# EE318.net
KiCad netlist of a schematic drawn in Altium Designer
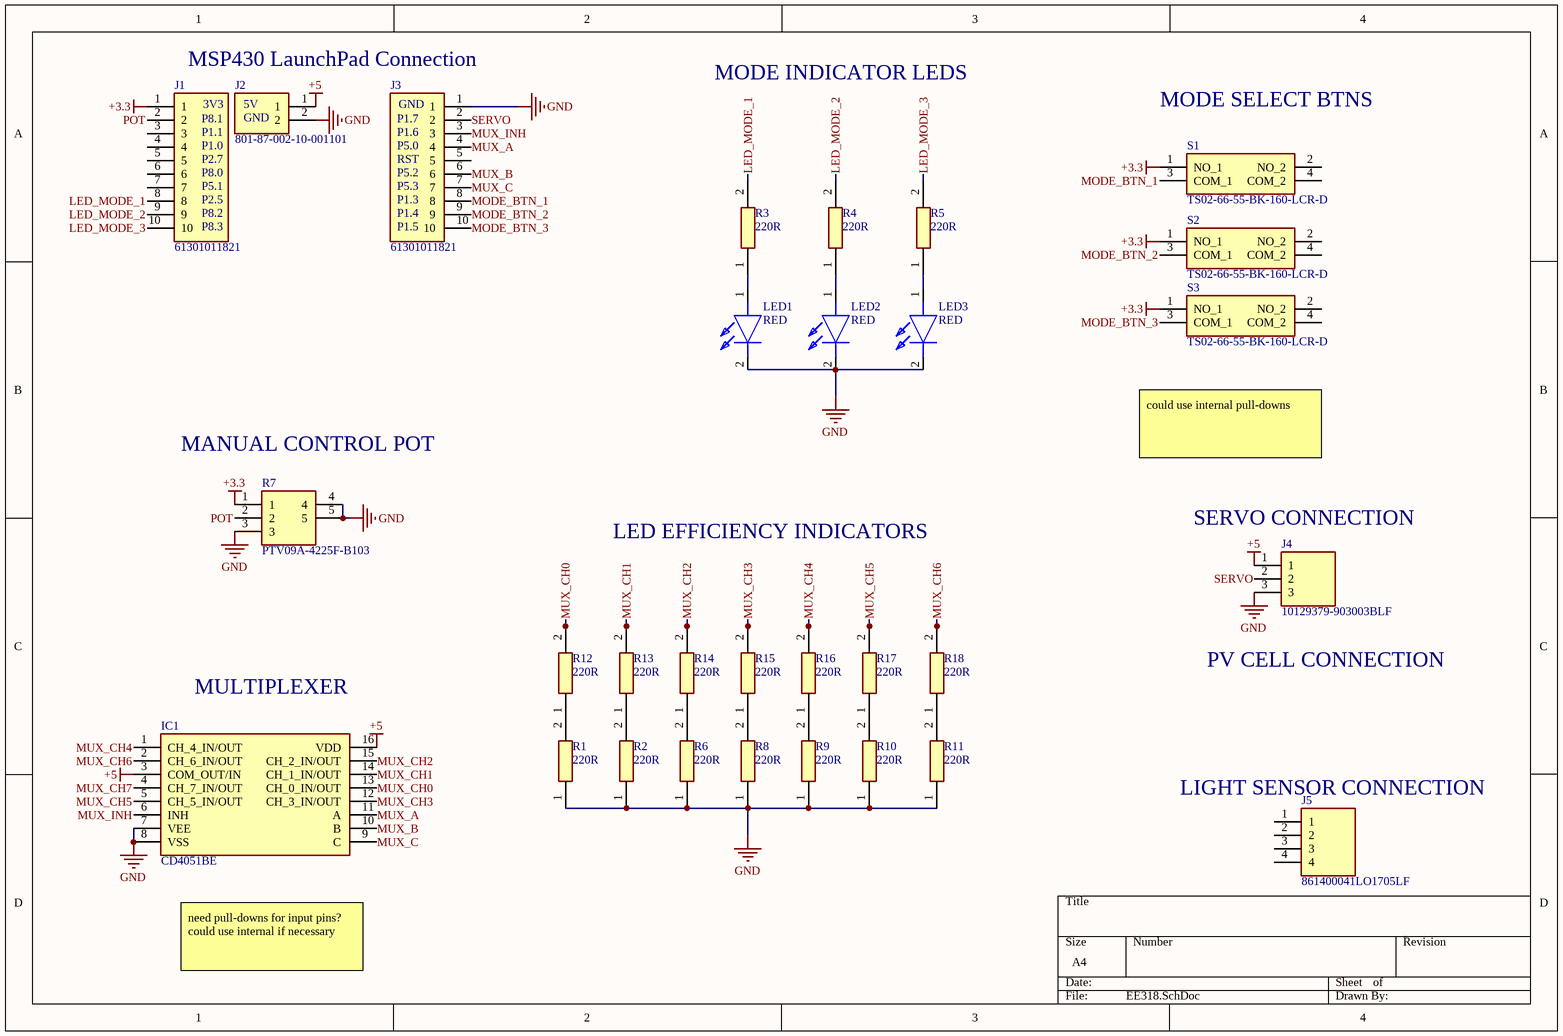
[diagram p0: EE318.SchDoc]

(export (version "E")
  (design (tool "Eeschema 10.0.6"))
  (components
    (comp (ref "IC1")
      (value "CD4051BE")
      (footprint "EE318-PcbLib:DIP794W53P254L1930H508Q16N")
      (description "Multiplexer")
      (fields (field (name "MOUSER PART NUMBER") "595-CD4051BE"))
      (libsource (lib "EE318-Schlib") (part "CD4051BE"))
    )
    (comp (ref "J1")
      (value "61301011821")
      (footprint "EE318-PcbLib:RHDR10W60P0X254_1X10_2590X250X850P")
      (description "Connector")
      (fields (field (name "MOUSER PART NUMBER") "710-61301011821"))
      (libsource (lib "") (part "61301011821_1"))
    )
    (comp (ref "J2")
      (value "801-87-002-10-001101")
      (footprint "EE318-PcbLib:RHDR2W60P0X254_1X2_508X254X700P")
      (description "Connector")
      (fields (field (name "MOUSER PART NUMBER") "437-8018700210001101"))
      (libsource (lib "EE318-Schlib") (part "801-87-002-10-001101"))
    )
    (comp (ref "J3")
      (value "61301011821")
      (footprint "EE318-PcbLib:RHDR10W60P0X254_1X10_2590X250X850P")
      (description "Connector")
      (fields (field (name "MOUSER PART NUMBER") "710-61301011821"))
      (libsource (lib "EE318-Schlib") (part "61301011821"))
    )
    (comp (ref "J4")
      (value "10129379-903003BLF")
      (footprint "EE318-PcbLib:10129379903003BLF")
      (description "Connector")
      (fields (field (name "MOUSER PART NUMBER") "649-1012937990303BLF"))
      (libsource (lib "EE318-Schlib") (part "10129379-903003BLF"))
    )
    (comp (ref "J5")
      (value "861400041LO1705LF")
      (footprint "EE318-PcbLib:HDRRA4W63P0X254_1X4_1016X260X264P")
      (description "Connector")
      (fields (field (name "MOUSER PART NUMBER") "649-86140041LO1705LF"))
      (libsource (lib "EE318-Schlib") (part "861400041LO1705LF"))
    )
    (comp (ref "LED1")
      (value "RED")
      (footprint "EE318-PcbLib:C503BRCNCW0Z0AA2")
      (description "LED")
      (fields
        (field (name "MANUFACTURER_PART_NUMBER") "C503B-RCN-CW0Z0AA2")
        (field (name "MOUSER PART NUMBER") "941-C503BRCNCW0Z0AA2")
      )
      (libsource (lib "EE318-Schlib") (part "C503B-RCN-CW0Z0AA2"))
    )
    (comp (ref "LED2")
      (value "RED")
      (footprint "EE318-PcbLib:C503BRCNCW0Z0AA2")
      (description "LED")
      (fields
        (field (name "MANUFACTURER_PART_NUMBER") "C503B-RCN-CW0Z0AA2")
        (field (name "MOUSER PART NUMBER") "941-C503BRCNCW0Z0AA2")
      )
      (libsource (lib "EE318-Schlib") (part "C503B-RCN-CW0Z0AA2"))
    )
    (comp (ref "LED3")
      (value "RED")
      (footprint "EE318-PcbLib:C503BRCNCW0Z0AA2")
      (description "LED")
      (fields
        (field (name "MANUFACTURER_PART_NUMBER") "C503B-RCN-CW0Z0AA2")
        (field (name "MOUSER PART NUMBER") "941-C503BRCNCW0Z0AA2")
      )
      (libsource (lib "EE318-Schlib") (part "C503B-RCN-CW0Z0AA2"))
    )
    (comp (ref "R1")
      (value "220R")
      (footprint "SamacSys:RESC3116X65N")
      (description "Resistor")
      (fields
        (field (name "MANUFACTURER_PART_NUMBER") "CRS1206QFX-1002ELF")
        (field (name "MOUSER PART NUMBER") "652-CRS1206QFX-1002E")
      )
      (libsource (lib "*") (part "CRS1206QFX-1002ELF"))
    )
    (comp (ref "R2")
      (value "220R")
      (footprint "SamacSys:RESC3116X65N")
      (description "Resistor")
      (fields
        (field (name "MANUFACTURER_PART_NUMBER") "CRS1206QFX-1002ELF")
        (field (name "MOUSER PART NUMBER") "652-CRS1206QFX-1002E")
      )
      (libsource (lib "*") (part "CRS1206QFX-1002ELF"))
    )
    (comp (ref "R3")
      (value "220R")
      (footprint "SamacSys:RESC3116X65N")
      (description "Resistor")
      (fields
        (field (name "MANUFACTURER_PART_NUMBER") "CRS1206QFX-1002ELF")
        (field (name "MOUSER PART NUMBER") "652-CRS1206QFX-1002E")
      )
      (libsource (lib "*") (part "CRS1206QFX-1002ELF"))
    )
    (comp (ref "R4")
      (value "220R")
      (footprint "SamacSys:RESC3116X65N")
      (description "Resistor")
      (fields
        (field (name "MANUFACTURER_PART_NUMBER") "CRS1206QFX-1002ELF")
        (field (name "MOUSER PART NUMBER") "652-CRS1206QFX-1002E")
      )
      (libsource (lib "*") (part "CRS1206QFX-1002ELF"))
    )
    (comp (ref "R5")
      (value "220R")
      (footprint "SamacSys:RESC3116X65N")
      (description "Resistor")
      (fields
        (field (name "MANUFACTURER_PART_NUMBER") "CRS1206QFX-1002ELF")
        (field (name "MOUSER PART NUMBER") "652-CRS1206QFX-1002E")
      )
      (libsource (lib "*") (part "CRS1206QFX-1002ELF"))
    )
    (comp (ref "R6")
      (value "220R")
      (footprint "SamacSys:RESC3116X65N")
      (description "Resistor")
      (fields
        (field (name "MANUFACTURER_PART_NUMBER") "CRS1206QFX-1002ELF")
        (field (name "MOUSER PART NUMBER") "652-CRS1206QFX-1002E")
      )
      (libsource (lib "*") (part "CRS1206QFX-1002ELF"))
    )
    (comp (ref "R7")
      (value "PTV09A-4225F-B103")
      (footprint "EE318-PcbLib:PTV09A4020FB103")
      (description "Potentiometer")
      (fields (field (name "RS PART NUMBER") "8274990P"))
      (libsource (lib "EE318-Schlib") (part "PTV09A-4225F-B103"))
    )
    (comp (ref "R8")
      (value "220R")
      (footprint "SamacSys:RESC3116X65N")
      (description "Resistor")
      (fields
        (field (name "MANUFACTURER_PART_NUMBER") "CRS1206QFX-1002ELF")
        (field (name "MOUSER PART NUMBER") "652-CRS1206QFX-1002E")
      )
      (libsource (lib "*") (part "CRS1206QFX-1002ELF"))
    )
    (comp (ref "R9")
      (value "220R")
      (footprint "SamacSys:RESC3116X65N")
      (description "Resistor")
      (fields
        (field (name "MANUFACTURER_PART_NUMBER") "CRS1206QFX-1002ELF")
        (field (name "MOUSER PART NUMBER") "652-CRS1206QFX-1002E")
      )
      (libsource (lib "*") (part "CRS1206QFX-1002ELF"))
    )
    (comp (ref "R10")
      (value "220R")
      (footprint "SamacSys:RESC3116X65N")
      (description "Resistor")
      (fields
        (field (name "MANUFACTURER_PART_NUMBER") "CRS1206QFX-1002ELF")
        (field (name "MOUSER PART NUMBER") "652-CRS1206QFX-1002E")
      )
      (libsource (lib "*") (part "CRS1206QFX-1002ELF"))
    )
    (comp (ref "R11")
      (value "220R")
      (footprint "SamacSys:RESC3116X65N")
      (description "Resistor")
      (fields
        (field (name "MANUFACTURER_PART_NUMBER") "CRS1206QFX-1002ELF")
        (field (name "MOUSER PART NUMBER") "652-CRS1206QFX-1002E")
      )
      (libsource (lib "*") (part "CRS1206QFX-1002ELF"))
    )
    (comp (ref "R12")
      (value "220R")
      (footprint "SamacSys:RESC3116X65N")
      (description "Resistor")
      (fields
        (field (name "MANUFACTURER_PART_NUMBER") "CRS1206QFX-1002ELF")
        (field (name "MOUSER PART NUMBER") "652-CRS1206QFX-1002E")
      )
      (libsource (lib "*") (part "CRS1206QFX-1002ELF"))
    )
    (comp (ref "R13")
      (value "220R")
      (footprint "SamacSys:RESC3116X65N")
      (description "Resistor")
      (fields
        (field (name "MANUFACTURER_PART_NUMBER") "CRS1206QFX-1002ELF")
        (field (name "MOUSER PART NUMBER") "652-CRS1206QFX-1002E")
      )
      (libsource (lib "*") (part "CRS1206QFX-1002ELF"))
    )
    (comp (ref "R14")
      (value "220R")
      (footprint "SamacSys:RESC3116X65N")
      (description "Resistor")
      (fields
        (field (name "MANUFACTURER_PART_NUMBER") "CRS1206QFX-1002ELF")
        (field (name "MOUSER PART NUMBER") "652-CRS1206QFX-1002E")
      )
      (libsource (lib "*") (part "CRS1206QFX-1002ELF"))
    )
    (comp (ref "R15")
      (value "220R")
      (footprint "SamacSys:RESC3116X65N")
      (description "Resistor")
      (fields
        (field (name "MANUFACTURER_PART_NUMBER") "CRS1206QFX-1002ELF")
        (field (name "MOUSER PART NUMBER") "652-CRS1206QFX-1002E")
      )
      (libsource (lib "*") (part "CRS1206QFX-1002ELF"))
    )
    (comp (ref "R16")
      (value "220R")
      (footprint "SamacSys:RESC3116X65N")
      (description "Resistor")
      (fields
        (field (name "MANUFACTURER_PART_NUMBER") "CRS1206QFX-1002ELF")
        (field (name "MOUSER PART NUMBER") "652-CRS1206QFX-1002E")
      )
      (libsource (lib "*") (part "CRS1206QFX-1002ELF"))
    )
    (comp (ref "R17")
      (value "220R")
      (footprint "SamacSys:RESC3116X65N")
      (description "Resistor")
      (fields
        (field (name "MANUFACTURER_PART_NUMBER") "CRS1206QFX-1002ELF")
        (field (name "MOUSER PART NUMBER") "652-CRS1206QFX-1002E")
      )
      (libsource (lib "*") (part "CRS1206QFX-1002ELF"))
    )
    (comp (ref "R18")
      (value "220R")
      (footprint "SamacSys:RESC3116X65N")
      (description "Resistor")
      (fields
        (field (name "MANUFACTURER_PART_NUMBER") "CRS1206QFX-1002ELF")
        (field (name "MOUSER PART NUMBER") "652-CRS1206QFX-1002E")
      )
      (libsource (lib "*") (part "CRS1206QFX-1002ELF"))
    )
    (comp (ref "S1")
      (value "TS02-66-55-BK-160-LCR-D")
      (footprint "EE318-PcbLib:TS026655BK160LCRD")
      (description "Switch")
      (fields (field (name "MOUSER PART NUMBER") "179-TS026655BK160LCR"))
      (libsource (lib "EE318-Schlib") (part "TS02-66-55-BK-160-LCR-D"))
    )
    (comp (ref "S2")
      (value "TS02-66-55-BK-160-LCR-D")
      (footprint "EE318-PcbLib:TS026655BK160LCRD")
      (description "Switch")
      (fields (field (name "MOUSER PART NUMBER") "179-TS026655BK160LCR"))
      (libsource (lib "EE318-Schlib") (part "TS02-66-55-BK-160-LCR-D"))
    )
    (comp (ref "S3")
      (value "TS02-66-55-BK-160-LCR-D")
      (footprint "EE318-PcbLib:TS026655BK160LCRD")
      (description "Switch")
      (fields (field (name "MOUSER PART NUMBER") "179-TS026655BK160LCR"))
      (libsource (lib "EE318-Schlib") (part "TS02-66-55-BK-160-LCR-D"))
    )
  )
  (nets
    (net (code "1") (name "+3.3") (class "Default")
      (node (ref "J1") (pin "1") (pinfunction "1_1") (pintype "passive"))
      (node (ref "R7") (pin "1") (pinfunction "1_1") (pintype "passive"))
      (node (ref "S1") (pin "1") (pinfunction "NO_1_1") (pintype "passive"))
      (node (ref "S2") (pin "1") (pinfunction "NO_1_1") (pintype "passive"))
      (node (ref "S3") (pin "1") (pinfunction "NO_1_1") (pintype "passive"))
    )
    (net (code "2") (name "+5") (class "Default")
      (node (ref "IC1") (pin "16") (pinfunction "VDD_16") (pintype "passive"))
      (node (ref "IC1") (pin "3") (pinfunction "COM_OUT/IN_3") (pintype "passive"))
      (node (ref "J2") (pin "1") (pinfunction "1_1") (pintype "passive"))
      (node (ref "J4") (pin "1") (pinfunction "1_1") (pintype "passive"))
    )
    (net (code "3") (name "/LED_MODE_1") (class "Default")
      (node (ref "J1") (pin "8") (pinfunction "8_8") (pintype "passive"))
      (node (ref "R3") (pin "2") (pinfunction "2_2") (pintype "passive"))
    )
    (net (code "4") (name "/LED_MODE_2") (class "Default")
      (node (ref "J1") (pin "9") (pinfunction "9_9") (pintype "passive"))
      (node (ref "R4") (pin "2") (pinfunction "2_2") (pintype "passive"))
    )
    (net (code "5") (name "/LED_MODE_3") (class "Default")
      (node (ref "J1") (pin "10") (pinfunction "10_10") (pintype "passive"))
      (node (ref "R5") (pin "2") (pinfunction "2_2") (pintype "passive"))
    )
    (net (code "6") (name "/MODE_BTN_1") (class "Default")
      (node (ref "J3") (pin "8") (pinfunction "8_8") (pintype "passive"))
      (node (ref "S1") (pin "3") (pinfunction "COM_1_3") (pintype "passive"))
    )
    (net (code "7") (name "/MODE_BTN_2") (class "Default")
      (node (ref "J3") (pin "9") (pinfunction "9_9") (pintype "passive"))
      (node (ref "S2") (pin "3") (pinfunction "COM_1_3") (pintype "passive"))
    )
    (net (code "8") (name "/MODE_BTN_3") (class "Default")
      (node (ref "J3") (pin "10") (pinfunction "10_10") (pintype "passive"))
      (node (ref "S3") (pin "3") (pinfunction "COM_1_3") (pintype "passive"))
    )
    (net (code "9") (name "/MUX_A") (class "Default")
      (node (ref "IC1") (pin "11") (pinfunction "A_11") (pintype "passive"))
      (node (ref "J3") (pin "4") (pinfunction "4_4") (pintype "passive"))
    )
    (net (code "10") (name "/MUX_B") (class "Default")
      (node (ref "IC1") (pin "10") (pinfunction "B_10") (pintype "passive"))
      (node (ref "J3") (pin "6") (pinfunction "6_6") (pintype "passive"))
    )
    (net (code "11") (name "/MUX_C") (class "Default")
      (node (ref "IC1") (pin "9") (pinfunction "C_9") (pintype "passive"))
      (node (ref "J3") (pin "7") (pinfunction "7_7") (pintype "passive"))
    )
    (net (code "12") (name "/MUX_CH0") (class "Default")
      (node (ref "IC1") (pin "13") (pinfunction "CH_0_IN/OUT_13") (pintype "passive"))
      (node (ref "R1") (pin "2") (pinfunction "2_2") (pintype "passive"))
      (node (ref "R12") (pin "2") (pinfunction "2_2") (pintype "passive"))
    )
    (net (code "13") (name "/MUX_CH1") (class "Default")
      (node (ref "IC1") (pin "14") (pinfunction "CH_1_IN/OUT_14") (pintype "passive"))
      (node (ref "R13") (pin "2") (pinfunction "2_2") (pintype "passive"))
      (node (ref "R2") (pin "2") (pinfunction "2_2") (pintype "passive"))
    )
    (net (code "14") (name "/MUX_CH2") (class "Default")
      (node (ref "IC1") (pin "15") (pinfunction "CH_2_IN/OUT_15") (pintype "passive"))
      (node (ref "R14") (pin "2") (pinfunction "2_2") (pintype "passive"))
      (node (ref "R6") (pin "2") (pinfunction "2_2") (pintype "passive"))
    )
    (net (code "15") (name "/MUX_CH3") (class "Default")
      (node (ref "IC1") (pin "12") (pinfunction "CH_3_IN/OUT_12") (pintype "passive"))
      (node (ref "R15") (pin "2") (pinfunction "2_2") (pintype "passive"))
      (node (ref "R8") (pin "2") (pinfunction "2_2") (pintype "passive"))
    )
    (net (code "16") (name "/MUX_CH4") (class "Default")
      (node (ref "IC1") (pin "1") (pinfunction "CH_4_IN/OUT_1") (pintype "passive"))
      (node (ref "R16") (pin "2") (pinfunction "2_2") (pintype "passive"))
      (node (ref "R9") (pin "2") (pinfunction "2_2") (pintype "passive"))
    )
    (net (code "17") (name "/MUX_CH5") (class "Default")
      (node (ref "IC1") (pin "5") (pinfunction "CH_5_IN/OUT_5") (pintype "passive"))
      (node (ref "R10") (pin "2") (pinfunction "2_2") (pintype "passive"))
      (node (ref "R17") (pin "2") (pinfunction "2_2") (pintype "passive"))
    )
    (net (code "18") (name "/MUX_CH6") (class "Default")
      (node (ref "IC1") (pin "2") (pinfunction "CH_6_IN/OUT_2") (pintype "passive"))
      (node (ref "R11") (pin "2") (pinfunction "2_2") (pintype "passive"))
      (node (ref "R18") (pin "2") (pinfunction "2_2") (pintype "passive"))
    )
    (net (code "19") (name "/MUX_CH7") (class "Default")
      (node (ref "IC1") (pin "4") (pinfunction "CH_7_IN/OUT_4") (pintype "passive"))
    )
    (net (code "20") (name "/MUX_INH") (class "Default")
      (node (ref "IC1") (pin "6") (pinfunction "INH_6") (pintype "passive"))
      (node (ref "J3") (pin "3") (pinfunction "3_3") (pintype "passive"))
    )
    (net (code "21") (name "/POT") (class "Default")
      (node (ref "J1") (pin "2") (pinfunction "2_2") (pintype "passive"))
      (node (ref "R7") (pin "2") (pinfunction "2_2") (pintype "passive"))
    )
    (net (code "22") (name "/SERVO") (class "Default")
      (node (ref "J3") (pin "2") (pinfunction "2_2") (pintype "passive"))
      (node (ref "J4") (pin "2") (pinfunction "2_2") (pintype "passive"))
    )
    (net (code "23") (name "GND") (class "Default")
      (node (ref "IC1") (pin "7") (pinfunction "VEE_7") (pintype "passive"))
      (node (ref "IC1") (pin "8") (pinfunction "VSS_8") (pintype "passive"))
      (node (ref "J2") (pin "2") (pinfunction "2_2") (pintype "passive"))
      (node (ref "J3") (pin "1") (pinfunction "1_1") (pintype "passive"))
      (node (ref "J4") (pin "3") (pinfunction "3_3") (pintype "passive"))
      (node (ref "LED1") (pin "2") (pinfunction "K_2") (pintype "passive"))
      (node (ref "LED2") (pin "2") (pinfunction "K_2") (pintype "passive"))
      (node (ref "LED3") (pin "2") (pinfunction "K_2") (pintype "passive"))
      (node (ref "R1") (pin "1") (pinfunction "1_1") (pintype "passive"))
      (node (ref "R10") (pin "1") (pinfunction "1_1") (pintype "passive"))
      (node (ref "R11") (pin "1") (pinfunction "1_1") (pintype "passive"))
      (node (ref "R2") (pin "1") (pinfunction "1_1") (pintype "passive"))
      (node (ref "R6") (pin "1") (pinfunction "1_1") (pintype "passive"))
      (node (ref "R7") (pin "3") (pinfunction "3_3") (pintype "passive"))
      (node (ref "R7") (pin "4") (pinfunction "4_4") (pintype "passive"))
      (node (ref "R7") (pin "5") (pinfunction "5_5") (pintype "passive"))
      (node (ref "R8") (pin "1") (pinfunction "1_1") (pintype "passive"))
      (node (ref "R9") (pin "1") (pinfunction "1_1") (pintype "passive"))
    )
    (net (code "24") (name "Net-(LED1-A)") (class "Default")
      (node (ref "LED1") (pin "1") (pinfunction "A_1") (pintype "passive"))
      (node (ref "R3") (pin "1") (pinfunction "1_1") (pintype "passive"))
    )
    (net (code "25") (name "Net-(LED2-A)") (class "Default")
      (node (ref "LED2") (pin "1") (pinfunction "A_1") (pintype "passive"))
      (node (ref "R4") (pin "1") (pinfunction "1_1") (pintype "passive"))
    )
    (net (code "26") (name "Net-(LED3-A)") (class "Default")
      (node (ref "LED3") (pin "1") (pinfunction "A_1") (pintype "passive"))
      (node (ref "R5") (pin "1") (pinfunction "1_1") (pintype "passive"))
    )
    (net (code "27") (name "unconnected-(J1-Pad3)") (class "Default")
      (node (ref "J1") (pin "3") (pinfunction "3_3") (pintype "passive"))
    )
    (net (code "28") (name "unconnected-(J1-Pad4)") (class "Default")
      (node (ref "J1") (pin "4") (pinfunction "4_4") (pintype "passive"))
    )
    (net (code "29") (name "unconnected-(J1-Pad5)") (class "Default")
      (node (ref "J1") (pin "5") (pinfunction "5_5") (pintype "passive"))
    )
    (net (code "30") (name "unconnected-(J1-Pad6)") (class "Default")
      (node (ref "J1") (pin "6") (pinfunction "6_6") (pintype "passive"))
    )
    (net (code "31") (name "unconnected-(J1-Pad7)") (class "Default")
      (node (ref "J1") (pin "7") (pinfunction "7_7") (pintype "passive"))
    )
    (net (code "32") (name "unconnected-(J3-Pad5)") (class "Default")
      (node (ref "J3") (pin "5") (pinfunction "5_5") (pintype "passive"))
    )
    (net (code "33") (name "unconnected-(J5-Pad1)") (class "Default")
      (node (ref "J5") (pin "1") (pinfunction "1_1") (pintype "passive"))
    )
    (net (code "34") (name "unconnected-(J5-Pad2)") (class "Default")
      (node (ref "J5") (pin "2") (pinfunction "2_2") (pintype "passive"))
    )
    (net (code "35") (name "unconnected-(J5-Pad3)") (class "Default")
      (node (ref "J5") (pin "3") (pinfunction "3_3") (pintype "passive"))
    )
    (net (code "36") (name "unconnected-(J5-Pad4)") (class "Default")
      (node (ref "J5") (pin "4") (pinfunction "4_4") (pintype "passive"))
    )
    (net (code "37") (name "unconnected-(R12-Pad1)") (class "Default")
      (node (ref "R12") (pin "1") (pinfunction "1_1") (pintype "passive"))
    )
    (net (code "38") (name "unconnected-(R13-Pad1)") (class "Default")
      (node (ref "R13") (pin "1") (pinfunction "1_1") (pintype "passive"))
    )
    (net (code "39") (name "unconnected-(R14-Pad1)") (class "Default")
      (node (ref "R14") (pin "1") (pinfunction "1_1") (pintype "passive"))
    )
    (net (code "40") (name "unconnected-(R15-Pad1)") (class "Default")
      (node (ref "R15") (pin "1") (pinfunction "1_1") (pintype "passive"))
    )
    (net (code "41") (name "unconnected-(R16-Pad1)") (class "Default")
      (node (ref "R16") (pin "1") (pinfunction "1_1") (pintype "passive"))
    )
    (net (code "42") (name "unconnected-(R17-Pad1)") (class "Default")
      (node (ref "R17") (pin "1") (pinfunction "1_1") (pintype "passive"))
    )
    (net (code "43") (name "unconnected-(R18-Pad1)") (class "Default")
      (node (ref "R18") (pin "1") (pinfunction "1_1") (pintype "passive"))
    )
    (net (code "44") (name "unconnected-(S1-COM_2-Pad4)") (class "Default")
      (node (ref "S1") (pin "4") (pinfunction "COM_2_4") (pintype "passive"))
    )
    (net (code "45") (name "unconnected-(S1-NO_2-Pad2)") (class "Default")
      (node (ref "S1") (pin "2") (pinfunction "NO_2_2") (pintype "passive"))
    )
    (net (code "46") (name "unconnected-(S2-COM_2-Pad4)") (class "Default")
      (node (ref "S2") (pin "4") (pinfunction "COM_2_4") (pintype "passive"))
    )
    (net (code "47") (name "unconnected-(S2-NO_2-Pad2)") (class "Default")
      (node (ref "S2") (pin "2") (pinfunction "NO_2_2") (pintype "passive"))
    )
    (net (code "48") (name "unconnected-(S3-COM_2-Pad4)") (class "Default")
      (node (ref "S3") (pin "4") (pinfunction "COM_2_4") (pintype "passive"))
    )
    (net (code "49") (name "unconnected-(S3-NO_2-Pad2)") (class "Default")
      (node (ref "S3") (pin "2") (pinfunction "NO_2_2") (pintype "passive"))
    )
  )
)
